# Connector.net
KiCad netlist of a schematic drawn in Altium Designer
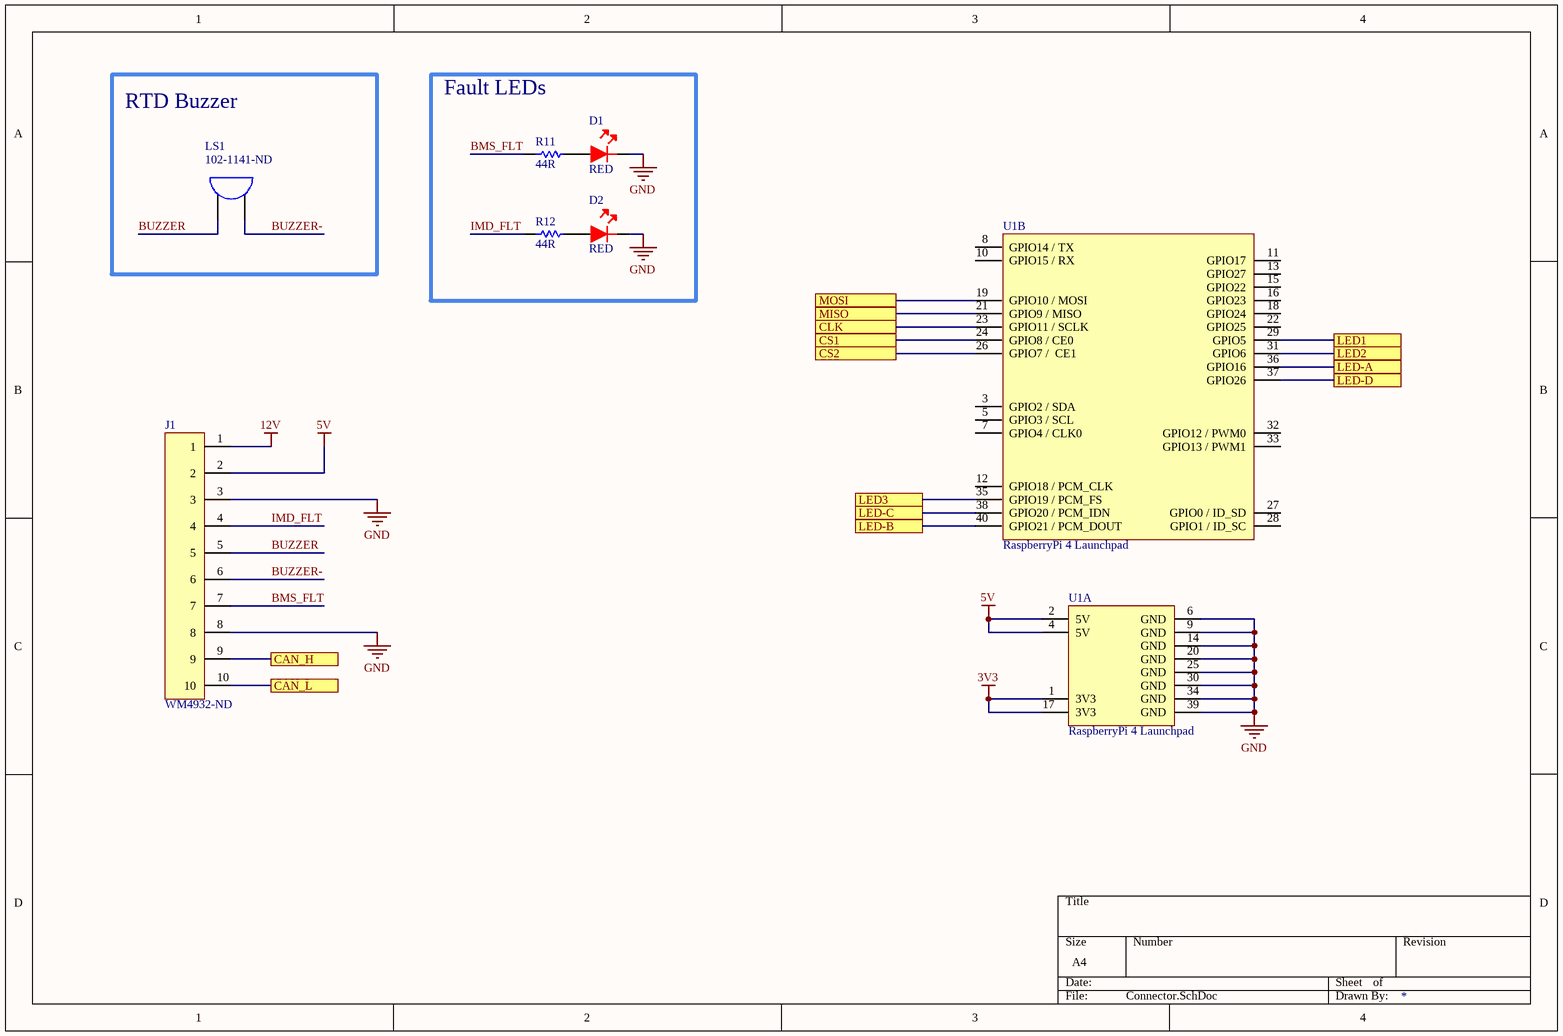
[diagram p0: Connector.SchDoc]

(export (version "E")
  (design (tool "Eeschema 10.0.6"))
  (components
    (comp (ref "D1")
      (value "RED")
      (footprint "LED")
      (description "2835 PLCC2 RED WLD: 620NM TYP. 1")
      (fields
        (field (name "MANUFACTURER") "QT-Brightek")
        (field (name "MANUFACTURER PART NUMBER") "QBHP686-RH")
      )
      (libsource (lib "BrakeLight") (part "RED_LED"))
    )
    (comp (ref "D2")
      (value "RED")
      (footprint "LED")
      (description "2835 PLCC2 RED WLD: 620NM TYP. 1")
      (fields
        (field (name "MANUFACTURER") "QT-Brightek")
        (field (name "MANUFACTURER PART NUMBER") "QBHP686-RH")
      )
      (libsource (lib "BrakeLight") (part "RED_LED"))
    )
    (comp (ref "J1")
      (value "WM4932-ND")
      (footprint "10PIN")
      (description "CONN HEADER R/A 10POS 2.54MM")
      (fields (field (name "MANUFACTURER") "Molex") (field (name "MANUFACTURER PART NUMBER") "0705530044"))
      (libsource (lib "Connectors") (part "10PIN"))
    )
    (comp (ref "LS1")
      (value "102-1141-ND")
      (footprint "Buzzer")
      (description "AUDIO PIEZO TRANSDUCER 30V TH")
      (fields (field (name "MANUFACTURER") "CUI") (field (name "MANUFACTURER PART NUMBER") "CEP-1116"))
      (libsource (lib "Misc") (part "Buzzer"))
    )
    (comp (ref "R11")
      (value "44R")
      (footprint "RES-0603")
      (fields
        (field (name "MANUFACTURER") "Panasonic")
        (field (name "MANUFACTURER PART NUMBER") "ERJ-3EKF44R2V")
        (field (name "TOLERANCE") "1%")
      )
      (libsource (lib "BrakeLight") (part "0603-44R"))
    )
    (comp (ref "R12")
      (value "44R")
      (footprint "RES-0603")
      (fields
        (field (name "MANUFACTURER") "Panasonic")
        (field (name "MANUFACTURER PART NUMBER") "ERJ-3EKF44R2V")
        (field (name "TOLERANCE") "1%")
      )
      (libsource (lib "BrakeLight") (part "0603-44R"))
    )
    (comp (ref "U1")
      (value "RaspberryPi 4 Launchpad")
      (footprint "Rpi Connector")
      (description "CONNECTOR DEV BOARD RaspberryPi 4")
      (fields
        (field (name "MANUFACTURER") "Sullins")
        (field (name "MANUFACTURER PART NUMBER") "PPPC202LFBN-RC")
      )
      (libsource (lib "WorkshopSlib") (part "RasPi4"))
    )
  )
  (nets
    (net (code "1") (name "/BMS_FLT") (class "Default")
      (node (ref "J1") (pin "7") (pinfunction "7_7") (pintype "passive"))
      (node (ref "R11") (pin "1") (pinfunction "1_1") (pintype "passive"))
    )
    (net (code "2") (name "/BUZZER") (class "Default")
      (node (ref "J1") (pin "5") (pinfunction "5_5") (pintype "passive"))
      (node (ref "LS1") (pin "1") (pinfunction "1_1") (pintype "passive"))
    )
    (net (code "3") (name "/BUZZER-") (class "Default")
      (node (ref "J1") (pin "6") (pinfunction "6_6") (pintype "passive"))
      (node (ref "LS1") (pin "2") (pinfunction "2_2") (pintype "passive"))
    )
    (net (code "4") (name "/CAN_H") (class "Default")
      (node (ref "J1") (pin "9") (pinfunction "9_9") (pintype "passive"))
    )
    (net (code "5") (name "/CAN_L") (class "Default")
      (node (ref "J1") (pin "10") (pinfunction "10_10") (pintype "passive"))
    )
    (net (code "6") (name "/CLK") (class "Default")
      (node (ref "U1") (pin "23") (pinfunction "GPIO11_/_SCLK_23") (pintype "passive"))
    )
    (net (code "7") (name "/CS1") (class "Default")
      (node (ref "U1") (pin "24") (pinfunction "GPIO8_/_CE0_24") (pintype "passive"))
    )
    (net (code "8") (name "/CS2") (class "Default")
      (node (ref "U1") (pin "26") (pinfunction "GPIO7_/__CE1_26") (pintype "passive"))
    )
    (net (code "9") (name "/IMD_FLT") (class "Default")
      (node (ref "J1") (pin "4") (pinfunction "4_4") (pintype "passive"))
      (node (ref "R12") (pin "1") (pinfunction "1_1") (pintype "passive"))
    )
    (net (code "10") (name "/LED-A") (class "Default")
      (node (ref "U1") (pin "36") (pinfunction "GPIO16_36") (pintype "passive"))
    )
    (net (code "11") (name "/LED-B") (class "Default")
      (node (ref "U1") (pin "40") (pinfunction "GPIO21_/_PCM_DOUT_40") (pintype "passive"))
    )
    (net (code "12") (name "/LED-C") (class "Default")
      (node (ref "U1") (pin "38") (pinfunction "GPIO20_/_PCM_IDN_38") (pintype "passive"))
    )
    (net (code "13") (name "/LED-D") (class "Default")
      (node (ref "U1") (pin "37") (pinfunction "GPIO26_37") (pintype "passive"))
    )
    (net (code "14") (name "/LED1") (class "Default")
      (node (ref "U1") (pin "29") (pinfunction "GPIO5_29") (pintype "passive"))
    )
    (net (code "15") (name "/LED2") (class "Default")
      (node (ref "U1") (pin "31") (pinfunction "GPIO6_31") (pintype "passive"))
    )
    (net (code "16") (name "/LED3") (class "Default")
      (node (ref "U1") (pin "35") (pinfunction "GPIO19_/_PCM_FS_35") (pintype "passive"))
    )
    (net (code "17") (name "/MISO") (class "Default")
      (node (ref "U1") (pin "21") (pinfunction "GPIO9_/_MISO_21") (pintype "passive"))
    )
    (net (code "18") (name "/MOSI") (class "Default")
      (node (ref "U1") (pin "19") (pinfunction "GPIO10_/_MOSI_19") (pintype "passive"))
    )
    (net (code "19") (name "3V3") (class "Default")
      (node (ref "U1") (pin "1") (pinfunction "3V3_1") (pintype "passive"))
      (node (ref "U1") (pin "17") (pinfunction "3V3_17") (pintype "passive"))
    )
    (net (code "20") (name "5V") (class "Default")
      (node (ref "J1") (pin "2") (pinfunction "2_2") (pintype "passive"))
      (node (ref "U1") (pin "2") (pinfunction "5V_2") (pintype "passive"))
      (node (ref "U1") (pin "4") (pinfunction "5V_4") (pintype "passive"))
    )
    (net (code "21") (name "12V") (class "Default")
      (node (ref "J1") (pin "1") (pinfunction "1_1") (pintype "passive"))
    )
    (net (code "22") (name "GND") (class "Default")
      (node (ref "D1") (pin "2") (pinfunction "2_2") (pintype "passive"))
      (node (ref "D2") (pin "2") (pinfunction "2_2") (pintype "passive"))
      (node (ref "J1") (pin "3") (pinfunction "3_3") (pintype "passive"))
      (node (ref "J1") (pin "8") (pinfunction "8_8") (pintype "passive"))
      (node (ref "U1") (pin "14") (pinfunction "GND_14") (pintype "passive"))
      (node (ref "U1") (pin "20") (pinfunction "GND_20") (pintype "passive"))
      (node (ref "U1") (pin "25") (pinfunction "GND_25") (pintype "passive"))
      (node (ref "U1") (pin "30") (pinfunction "GND_30") (pintype "passive"))
      (node (ref "U1") (pin "34") (pinfunction "GND_34") (pintype "passive"))
      (node (ref "U1") (pin "39") (pinfunction "GND_39") (pintype "passive"))
      (node (ref "U1") (pin "6") (pinfunction "GND_6") (pintype "passive"))
      (node (ref "U1") (pin "9") (pinfunction "GND_9") (pintype "passive"))
    )
    (net (code "23") (name "Net-(D1-Pad1)") (class "Default")
      (node (ref "D1") (pin "1") (pinfunction "1_1") (pintype "passive"))
      (node (ref "R11") (pin "2") (pinfunction "2_2") (pintype "passive"))
    )
    (net (code "24") (name "Net-(D2-Pad1)") (class "Default")
      (node (ref "D2") (pin "1") (pinfunction "1_1") (pintype "passive"))
      (node (ref "R12") (pin "2") (pinfunction "2_2") (pintype "passive"))
    )
    (net (code "25") (name "unconnected-(U1B-GPIO0_{slash}_ID_SD-Pad27)") (class "Default")
      (node (ref "U1") (pin "27") (pinfunction "GPIO0_/_ID_SD_27") (pintype "passive"))
    )
    (net (code "26") (name "unconnected-(U1B-GPIO1_{slash}_ID_SC-Pad28)") (class "Default")
      (node (ref "U1") (pin "28") (pinfunction "GPIO1_/_ID_SC_28") (pintype "passive"))
    )
    (net (code "27") (name "unconnected-(U1B-GPIO2_{slash}_SDA-Pad3)") (class "Default")
      (node (ref "U1") (pin "3") (pinfunction "GPIO2_/_SDA_3") (pintype "passive"))
    )
    (net (code "28") (name "unconnected-(U1B-GPIO3_{slash}_SCL-Pad5)") (class "Default")
      (node (ref "U1") (pin "5") (pinfunction "GPIO3_/_SCL_5") (pintype "passive"))
    )
    (net (code "29") (name "unconnected-(U1B-GPIO4_{slash}_CLK0-Pad7)") (class "Default")
      (node (ref "U1") (pin "7") (pinfunction "GPIO4_/_CLK0_7") (pintype "passive"))
    )
    (net (code "30") (name "unconnected-(U1B-GPIO12_{slash}_PWM0-Pad32)") (class "Default")
      (node (ref "U1") (pin "32") (pinfunction "GPIO12_/_PWM0_32") (pintype "passive"))
    )
    (net (code "31") (name "unconnected-(U1B-GPIO13_{slash}_PWM1-Pad33)") (class "Default")
      (node (ref "U1") (pin "33") (pinfunction "GPIO13_/_PWM1_33") (pintype "passive"))
    )
    (net (code "32") (name "unconnected-(U1B-GPIO14_{slash}_TX-Pad8)") (class "Default")
      (node (ref "U1") (pin "8") (pinfunction "GPIO14_/_TX_8") (pintype "passive"))
    )
    (net (code "33") (name "unconnected-(U1B-GPIO15_{slash}_RX-Pad10)") (class "Default")
      (node (ref "U1") (pin "10") (pinfunction "GPIO15_/_RX_10") (pintype "passive"))
    )
    (net (code "34") (name "unconnected-(U1B-GPIO17-Pad11)") (class "Default")
      (node (ref "U1") (pin "11") (pinfunction "GPIO17_11") (pintype "passive"))
    )
    (net (code "35") (name "unconnected-(U1B-GPIO18_{slash}_PCM_CLK-Pad12)") (class "Default")
      (node (ref "U1") (pin "12") (pinfunction "GPIO18_/_PCM_CLK_12") (pintype "passive"))
    )
    (net (code "36") (name "unconnected-(U1B-GPIO22-Pad15)") (class "Default")
      (node (ref "U1") (pin "15") (pinfunction "GPIO22_15") (pintype "passive"))
    )
    (net (code "37") (name "unconnected-(U1B-GPIO23-Pad16)") (class "Default")
      (node (ref "U1") (pin "16") (pinfunction "GPIO23_16") (pintype "passive"))
    )
    (net (code "38") (name "unconnected-(U1B-GPIO24-Pad18)") (class "Default")
      (node (ref "U1") (pin "18") (pinfunction "GPIO24_18") (pintype "passive"))
    )
    (net (code "39") (name "unconnected-(U1B-GPIO25-Pad22)") (class "Default")
      (node (ref "U1") (pin "22") (pinfunction "GPIO25_22") (pintype "passive"))
    )
    (net (code "40") (name "unconnected-(U1B-GPIO27-Pad13)") (class "Default")
      (node (ref "U1") (pin "13") (pinfunction "GPIO27_13") (pintype "passive"))
    )
  )
)
